# Front_Distribution.net
KiCad netlist of a schematic drawn in Altium Designer
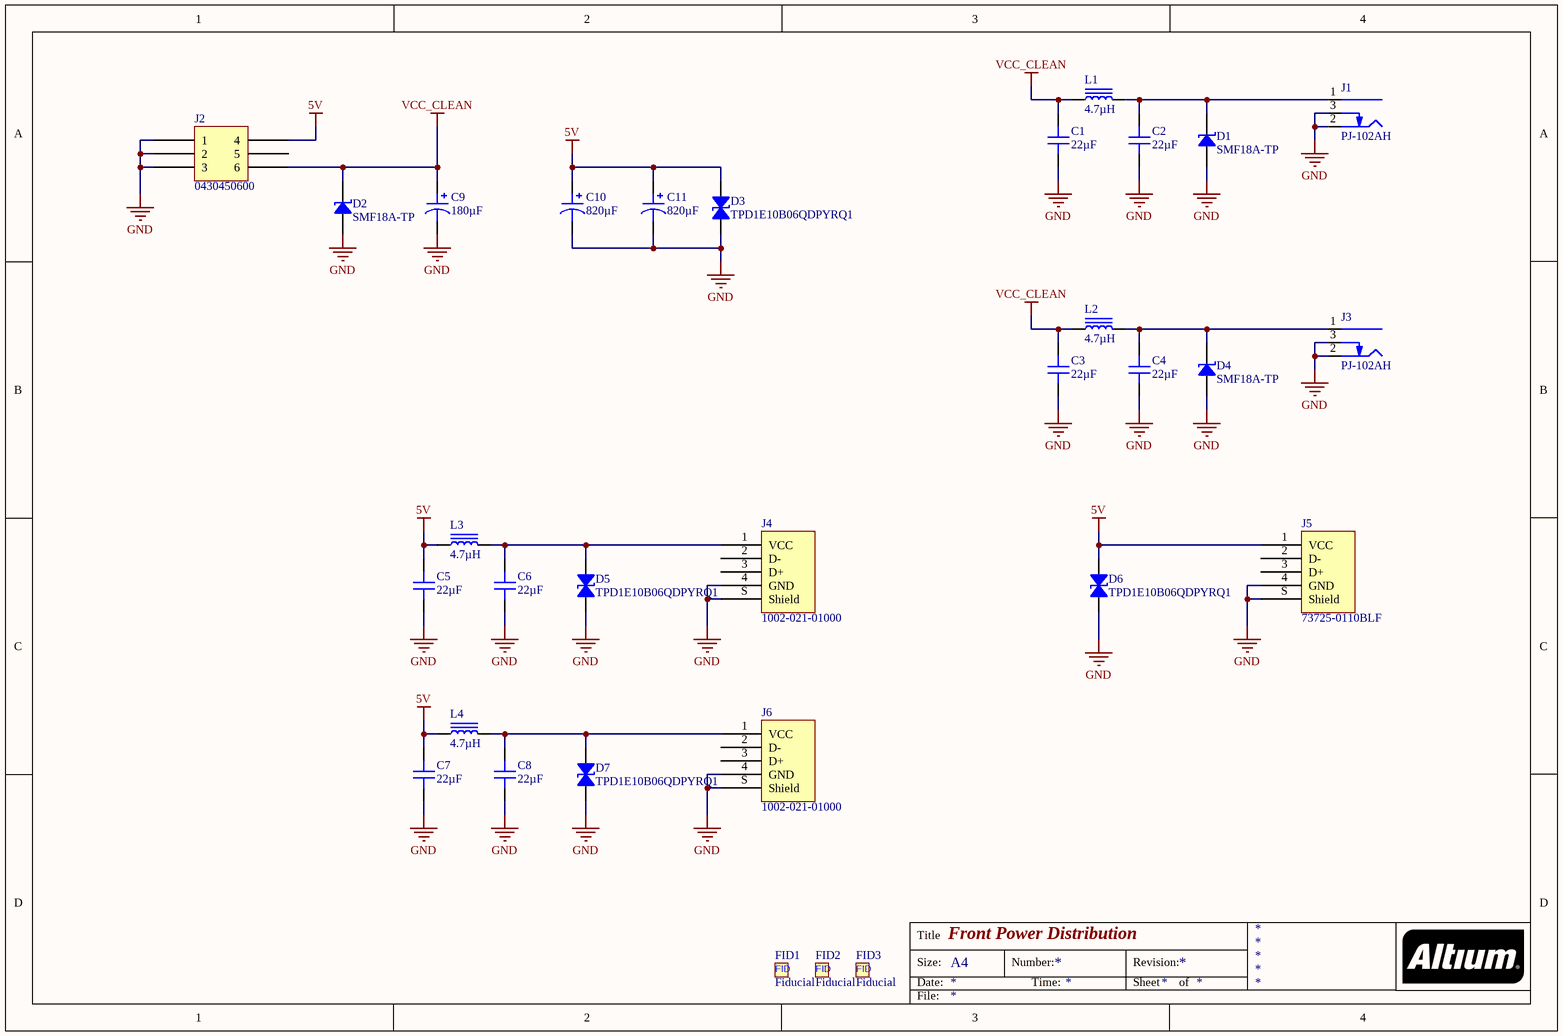
[diagram p0: Front Distribution.SchDoc]

(export (version "E")
  (design (tool "Eeschema 10.0.6"))
  (components
    (comp (ref "C1")
      (value "22µF")
      (footprint "CAP 1210_3225 - 2.8MM")
      (description "CAP CER 22UF 25V X5R 1210")
      (fields
        (field (name "PART NUMBER") "CL32A226KAJNNNE")
        (field (name "MANUFACTURER") "Samsung Electro-Mechanics")
      )
      (libsource (lib "Celestial Altium Library - altium_library") (part "Capacitor"))
    )
    (comp (ref "C2")
      (value "22µF")
      (footprint "CAP 1210_3225 - 2.8MM")
      (description "CAP CER 22UF 25V X5R 1210")
      (fields
        (field (name "PART NUMBER") "CL32A226KAJNNNE")
        (field (name "MANUFACTURER") "Samsung Electro-Mechanics")
      )
      (libsource (lib "Celestial Altium Library - altium_library") (part "Capacitor"))
    )
    (comp (ref "C3")
      (value "22µF")
      (footprint "CAP 1210_3225 - 2.8MM")
      (description "CAP CER 22UF 25V X5R 1210")
      (fields
        (field (name "PART NUMBER") "CL32A226KAJNNNE")
        (field (name "MANUFACTURER") "Samsung Electro-Mechanics")
      )
      (libsource (lib "Celestial Altium Library - altium_library") (part "Capacitor"))
    )
    (comp (ref "C4")
      (value "22µF")
      (footprint "CAP 1210_3225 - 2.8MM")
      (description "CAP CER 22UF 25V X5R 1210")
      (fields
        (field (name "PART NUMBER") "CL32A226KAJNNNE")
        (field (name "MANUFACTURER") "Samsung Electro-Mechanics")
      )
      (libsource (lib "Celestial Altium Library - altium_library") (part "Capacitor"))
    )
    (comp (ref "C5")
      (value "22µF")
      (footprint "CAP 1210_3225 - 2.8MM")
      (description "CAP CER 22UF 25V X5R 1210")
      (fields
        (field (name "PART NUMBER") "CL32A226KAJNNNE")
        (field (name "MANUFACTURER") "Samsung Electro-Mechanics")
      )
      (libsource (lib "Celestial Altium Library - altium_library") (part "Capacitor"))
    )
    (comp (ref "C6")
      (value "22µF")
      (footprint "CAP 1210_3225 - 2.8MM")
      (description "CAP CER 22UF 25V X5R 1210")
      (fields
        (field (name "PART NUMBER") "CL32A226KAJNNNE")
        (field (name "MANUFACTURER") "Samsung Electro-Mechanics")
      )
      (libsource (lib "Celestial Altium Library - altium_library") (part "Capacitor"))
    )
    (comp (ref "C7")
      (value "22µF")
      (footprint "CAP 1210_3225 - 2.8MM")
      (description "CAP CER 22UF 25V X5R 1210")
      (fields
        (field (name "PART NUMBER") "CL32A226KAJNNNE")
        (field (name "MANUFACTURER") "Samsung Electro-Mechanics")
      )
      (libsource (lib "Celestial Altium Library - altium_library") (part "Capacitor"))
    )
    (comp (ref "C8")
      (value "22µF")
      (footprint "CAP 1210_3225 - 2.8MM")
      (description "CAP CER 22UF 25V X5R 1210")
      (fields
        (field (name "PART NUMBER") "CL32A226KAJNNNE")
        (field (name "MANUFACTURER") "Samsung Electro-Mechanics")
      )
      (libsource (lib "Celestial Altium Library - altium_library") (part "Capacitor"))
    )
    (comp (ref "C9")
      (value "180µF")
      (footprint "CAP ALSMD POLY 8.3MM H7.0MM")
      (description "CAP ALUM POLY 180UF 20% 20V SMD")
      (fields
        (field (name "PART NUMBER") "APXG200ARA181MH70G")
        (field (name "MANUFACTURER") "United Chemi-Con")
      )
      (libsource (lib "Celestial Altium Library - altium_library") (part "Polarised Capacitor"))
    )
    (comp (ref "C10")
      (value "820µF")
      (footprint "CAP ALSMD POLY 8.3MM H10.0MM")
      (description "CAP ALUM POLY 820UF 20% 6.3V SMD")
      (fields (field (name "PART NUMBER") "A765KN827M0JLAE010") (field (name "MANUFACTURER") "KEMET"))
      (libsource (lib "Celestial Altium Library - altium_library") (part "Polarised Capacitor"))
    )
    (comp (ref "C11")
      (value "820µF")
      (footprint "CAP ALSMD POLY 8.3MM H10.0MM")
      (description "CAP ALUM POLY 820UF 20% 6.3V SMD")
      (fields (field (name "PART NUMBER") "A765KN827M0JLAE010") (field (name "MANUFACTURER") "KEMET"))
      (libsource (lib "Celestial Altium Library - altium_library") (part "Polarised Capacitor"))
    )
    (comp (ref "D1")
      (value "SMF18A-TP")
      (footprint "SOD123F")
      (description "TVS DIODE 18V 29.2V SOD123FL")
      (fields (field (name "MANUFACTURER") "Micro Commercial Co"))
      (libsource (lib "Celestial Altium Library - altium_library") (part "DIODE TVS UNI"))
    )
    (comp (ref "D2")
      (value "SMF18A-TP")
      (footprint "SOD123F")
      (description "TVS DIODE 18V 29.2V SOD123FL")
      (fields (field (name "MANUFACTURER") "Micro Commercial Co"))
      (libsource (lib "Celestial Altium Library - altium_library") (part "DIODE TVS UNI"))
    )
    (comp (ref "D3")
      (value "TPD1E10B06QDPYRQ1")
      (footprint "0402")
      (description "TVS DIODE 5.5V 14V 2X1SON")
      (fields (field (name "MANUFACTURER") "Texas Instruments"))
      (libsource (lib "Celestial Altium Library - altium_library") (part "Diode TVS"))
    )
    (comp (ref "D4")
      (value "SMF18A-TP")
      (footprint "SOD123F")
      (description "TVS DIODE 18V 29.2V SOD123FL")
      (fields (field (name "MANUFACTURER") "Micro Commercial Co"))
      (libsource (lib "Celestial Altium Library - altium_library") (part "DIODE TVS UNI"))
    )
    (comp (ref "D5")
      (value "TPD1E10B06QDPYRQ1")
      (footprint "0402")
      (description "TVS DIODE 5.5V 14V 2X1SON")
      (fields (field (name "MANUFACTURER") "Texas Instruments"))
      (libsource (lib "Celestial Altium Library - altium_library") (part "Diode TVS"))
    )
    (comp (ref "D6")
      (value "TPD1E10B06QDPYRQ1")
      (footprint "0402")
      (description "TVS DIODE 5.5V 14V 2X1SON")
      (fields (field (name "MANUFACTURER") "Texas Instruments"))
      (libsource (lib "Celestial Altium Library - altium_library") (part "Diode TVS"))
    )
    (comp (ref "D7")
      (value "TPD1E10B06QDPYRQ1")
      (footprint "0402")
      (description "TVS DIODE 5.5V 14V 2X1SON")
      (fields (field (name "MANUFACTURER") "Texas Instruments"))
      (libsource (lib "Celestial Altium Library - altium_library") (part "Diode TVS"))
    )
    (comp (ref "FID1")
      (value "Fiducial")
      (footprint "Fiducial-1mm")
      (libsource (lib "CelestialUseful") (part "Fiducial"))
    )
    (comp (ref "FID2")
      (value "Fiducial")
      (footprint "Fiducial-1mm")
      (libsource (lib "CelestialUseful") (part "Fiducial"))
    )
    (comp (ref "FID3")
      (value "Fiducial")
      (footprint "Fiducial-1mm")
      (libsource (lib "CelestialUseful") (part "Fiducial"))
    )
    (comp (ref "J1")
      (value "PJ-102AH")
      (footprint "CUI PJ-102AH")
      (description "CONN PWR JACK 2X5.5MM SOLDER")
      (fields (field (name "MANUFACTURER") "CUI Devices"))
      (libsource (lib "Celestial Altium Library - altium_library") (part "Barrel Connector"))
    )
    (comp (ref "J2")
      (value "0430450600")
      (footprint "MOLEX MICRO-FIT 3.0 0430450600")
      (description "CONN HEADER R/A 6POS 3MM")
      (fields (field (name "MANUFACTURER") "Molex"))
      (libsource (lib "Celestial Altium Library - altium_library") (part "2x3 Pin"))
    )
    (comp (ref "J3")
      (value "PJ-102AH")
      (footprint "CUI PJ-102AH")
      (description "CONN PWR JACK 2X5.5MM SOLDER")
      (fields (field (name "MANUFACTURER") "CUI Devices"))
      (libsource (lib "Celestial Altium Library - altium_library") (part "Barrel Connector"))
    )
    (comp (ref "J4")
      (value "1002-021-01000")
      (footprint "CNC TECH 1002-021-01000")
      (description "CONN RCPT USB2.0 TYPEA 4POS VERT")
      (fields (field (name "MANUFACTURER") "CNC Tech"))
      (libsource (lib "Celestial Altium Library - altium_library") (part "USB 2.0 TYPE A"))
    )
    (comp (ref "J5")
      (value "73725-0110BLF")
      (footprint "AMPHENOL USB 73725-0110BLF")
      (description "CONN RCPT USB2.0 TYPEA 4POS R/A")
      (fields (field (name "MANUFACTURER") "Amphenol ICC (FCI)"))
      (libsource (lib "Celestial Altium Library - altium_library") (part "USB 2.0 TYPE A"))
    )
    (comp (ref "J6")
      (value "1002-021-01000")
      (footprint "CNC TECH 1002-021-01000")
      (description "CONN RCPT USB2.0 TYPEA 4POS VERT")
      (fields (field (name "MANUFACTURER") "CNC Tech"))
      (libsource (lib "Celestial Altium Library - altium_library") (part "USB 2.0 TYPE A"))
    )
    (comp (ref "L1")
      (value "4.7µH")
      (footprint "TAIYO YUDEN NRS5030")
      (description "FIXED IND 4.7UH 2.6A 35 MOHM SMD")
      (fields (field (name "PART NUMBER") "NRS5030T4R7MMGJ") (field (name "MANUFACTURER") "Taiyo Yuden"))
      (libsource (lib "Celestial Altium Library - altium_library") (part "Inductor"))
    )
    (comp (ref "L2")
      (value "4.7µH")
      (footprint "TAIYO YUDEN NRS5030")
      (description "FIXED IND 4.7UH 2.6A 35 MOHM SMD")
      (fields (field (name "PART NUMBER") "NRS5030T4R7MMGJ") (field (name "MANUFACTURER") "Taiyo Yuden"))
      (libsource (lib "Celestial Altium Library - altium_library") (part "Inductor"))
    )
    (comp (ref "L3")
      (value "4.7µH")
      (footprint "TAIYO YUDEN NRS5030")
      (description "FIXED IND 4.7UH 2.6A 35 MOHM SMD")
      (fields (field (name "PART NUMBER") "NRS5030T4R7MMGJ") (field (name "MANUFACTURER") "Taiyo Yuden"))
      (libsource (lib "Celestial Altium Library - altium_library") (part "Inductor"))
    )
    (comp (ref "L4")
      (value "4.7µH")
      (footprint "TAIYO YUDEN NRS5030")
      (description "FIXED IND 4.7UH 2.6A 35 MOHM SMD")
      (fields (field (name "PART NUMBER") "NRS5030T4R7MMGJ") (field (name "MANUFACTURER") "Taiyo Yuden"))
      (libsource (lib "Celestial Altium Library - altium_library") (part "Inductor"))
    )
  )
  (nets
    (net (code "1") (name "5V") (class "Default")
      (node (ref "C10") (pin "1") (pinfunction "1_1") (pintype "passive"))
      (node (ref "C11") (pin "1") (pinfunction "1_1") (pintype "passive"))
      (node (ref "C5") (pin "2") (pinfunction "2_2") (pintype "passive"))
      (node (ref "C7") (pin "2") (pinfunction "2_2") (pintype "passive"))
      (node (ref "D3") (pin "2") (pinfunction "2_2") (pintype "passive"))
      (node (ref "D6") (pin "2") (pinfunction "2_2") (pintype "passive"))
      (node (ref "J2") (pin "4") (pinfunction "4_4") (pintype "passive"))
      (node (ref "J5") (pin "1") (pinfunction "VCC_1") (pintype "passive"))
      (node (ref "L3") (pin "1") (pinfunction "1_1") (pintype "passive"))
      (node (ref "L4") (pin "1") (pinfunction "1_1") (pintype "passive"))
    )
    (net (code "2") (name "GND") (class "Default")
      (node (ref "C1") (pin "1") (pinfunction "1_1") (pintype "passive"))
      (node (ref "C10") (pin "2") (pinfunction "2_2") (pintype "passive"))
      (node (ref "C11") (pin "2") (pinfunction "2_2") (pintype "passive"))
      (node (ref "C2") (pin "1") (pinfunction "1_1") (pintype "passive"))
      (node (ref "C3") (pin "1") (pinfunction "1_1") (pintype "passive"))
      (node (ref "C4") (pin "1") (pinfunction "1_1") (pintype "passive"))
      (node (ref "C5") (pin "1") (pinfunction "1_1") (pintype "passive"))
      (node (ref "C6") (pin "1") (pinfunction "1_1") (pintype "passive"))
      (node (ref "C7") (pin "1") (pinfunction "1_1") (pintype "passive"))
      (node (ref "C8") (pin "1") (pinfunction "1_1") (pintype "passive"))
      (node (ref "C9") (pin "2") (pinfunction "2_2") (pintype "passive"))
      (node (ref "D1") (pin "1") (pinfunction "1_1") (pintype "passive"))
      (node (ref "D2") (pin "1") (pinfunction "1_1") (pintype "passive"))
      (node (ref "D3") (pin "1") (pinfunction "1_1") (pintype "passive"))
      (node (ref "D4") (pin "1") (pinfunction "1_1") (pintype "passive"))
      (node (ref "D5") (pin "1") (pinfunction "1_1") (pintype "passive"))
      (node (ref "D6") (pin "1") (pinfunction "1_1") (pintype "passive"))
      (node (ref "D7") (pin "1") (pinfunction "1_1") (pintype "passive"))
      (node (ref "J1") (pin "2") (pinfunction "Outer_2") (pintype "passive"))
      (node (ref "J1") (pin "3") (pinfunction "SW_3") (pintype "passive"))
      (node (ref "J2") (pin "1") (pinfunction "1_1") (pintype "passive"))
      (node (ref "J2") (pin "2") (pinfunction "2_2") (pintype "passive"))
      (node (ref "J2") (pin "3") (pinfunction "3_3") (pintype "passive"))
      (node (ref "J3") (pin "2") (pinfunction "Outer_2") (pintype "passive"))
      (node (ref "J3") (pin "3") (pinfunction "SW_3") (pintype "passive"))
      (node (ref "J4") (pin "4") (pinfunction "GND_4") (pintype "passive"))
      (node (ref "J4") (pin "S") (pinfunction "Shield_S") (pintype "passive"))
      (node (ref "J5") (pin "4") (pinfunction "GND_4") (pintype "passive"))
      (node (ref "J5") (pin "S") (pinfunction "Shield_S") (pintype "passive"))
      (node (ref "J6") (pin "4") (pinfunction "GND_4") (pintype "passive"))
      (node (ref "J6") (pin "S") (pinfunction "Shield_S") (pintype "passive"))
    )
    (net (code "3") (name "Net-(J1-Centre)") (class "Default")
      (node (ref "C2") (pin "2") (pinfunction "2_2") (pintype "passive"))
      (node (ref "D1") (pin "2") (pinfunction "2_2") (pintype "passive"))
      (node (ref "J1") (pin "1") (pinfunction "Centre_1") (pintype "passive"))
      (node (ref "L1") (pin "2") (pinfunction "2_2") (pintype "passive"))
    )
    (net (code "4") (name "Net-(J3-Centre)") (class "Default")
      (node (ref "C4") (pin "2") (pinfunction "2_2") (pintype "passive"))
      (node (ref "D4") (pin "2") (pinfunction "2_2") (pintype "passive"))
      (node (ref "J3") (pin "1") (pinfunction "Centre_1") (pintype "passive"))
      (node (ref "L2") (pin "2") (pinfunction "2_2") (pintype "passive"))
    )
    (net (code "5") (name "Net-(J4-VCC)") (class "Default")
      (node (ref "C6") (pin "2") (pinfunction "2_2") (pintype "passive"))
      (node (ref "D5") (pin "2") (pinfunction "2_2") (pintype "passive"))
      (node (ref "J4") (pin "1") (pinfunction "VCC_1") (pintype "passive"))
      (node (ref "L3") (pin "2") (pinfunction "2_2") (pintype "passive"))
    )
    (net (code "6") (name "Net-(J6-VCC)") (class "Default")
      (node (ref "C8") (pin "2") (pinfunction "2_2") (pintype "passive"))
      (node (ref "D7") (pin "2") (pinfunction "2_2") (pintype "passive"))
      (node (ref "J6") (pin "1") (pinfunction "VCC_1") (pintype "passive"))
      (node (ref "L4") (pin "2") (pinfunction "2_2") (pintype "passive"))
    )
    (net (code "7") (name "VCC_CLEAN") (class "Default")
      (node (ref "C1") (pin "2") (pinfunction "2_2") (pintype "passive"))
      (node (ref "C3") (pin "2") (pinfunction "2_2") (pintype "passive"))
      (node (ref "C9") (pin "1") (pinfunction "1_1") (pintype "passive"))
      (node (ref "D2") (pin "2") (pinfunction "2_2") (pintype "passive"))
      (node (ref "J2") (pin "6") (pinfunction "6_6") (pintype "passive"))
      (node (ref "L1") (pin "1") (pinfunction "1_1") (pintype "passive"))
      (node (ref "L2") (pin "1") (pinfunction "1_1") (pintype "passive"))
    )
    (net (code "8") (name "unconnected-(J2-Pad5)") (class "Default")
      (node (ref "J2") (pin "5") (pinfunction "5_5") (pintype "passive"))
    )
    (net (code "9") (name "unconnected-(J4-D+-Pad3)") (class "Default")
      (node (ref "J4") (pin "3") (pinfunction "D+_3") (pintype "passive"))
    )
    (net (code "10") (name "unconnected-(J4-D--Pad2)") (class "Default")
      (node (ref "J4") (pin "2") (pinfunction "D-_2") (pintype "passive"))
    )
    (net (code "11") (name "unconnected-(J5-D+-Pad3)") (class "Default")
      (node (ref "J5") (pin "3") (pinfunction "D+_3") (pintype "passive"))
    )
    (net (code "12") (name "unconnected-(J5-D--Pad2)") (class "Default")
      (node (ref "J5") (pin "2") (pinfunction "D-_2") (pintype "passive"))
    )
    (net (code "13") (name "unconnected-(J6-D+-Pad3)") (class "Default")
      (node (ref "J6") (pin "3") (pinfunction "D+_3") (pintype "passive"))
    )
    (net (code "14") (name "unconnected-(J6-D--Pad2)") (class "Default")
      (node (ref "J6") (pin "2") (pinfunction "D-_2") (pintype "passive"))
    )
  )
)
